# Mosquito.net
KiCad netlist of a schematic drawn in EAGLE
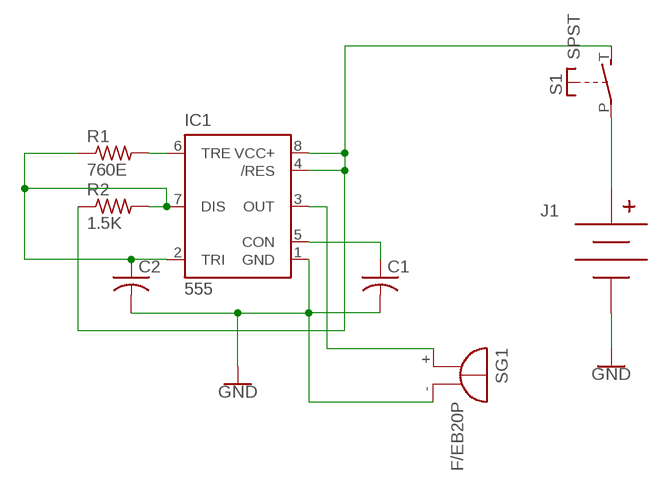
[diagram p0: schematic, sheet 1]

(export (version "E")
  (design (tool "Eeschema 10.0.6"))
  (components
    (comp (ref "C1")
      (value "C-US025-024X044")
      (footprint "eagle-import:C025-024X044")
      (libsource (lib "eagle-import") (part "C-US025-024X044"))
    )
    (comp (ref "C2")
      (value "C-US025-024X044")
      (footprint "eagle-import:C025-024X044")
      (libsource (lib "eagle-import") (part "C-US025-024X044"))
    )
    (comp (ref "IC1")
      (value "555")
      (footprint "eagle-import:DIP08")
      (libsource (lib "eagle-import") (part "555P"))
    )
    (comp (ref "J1")
      (value "BC9VPC")
      (footprint "eagle-import:BC9VPC")
      (libsource (lib "eagle-import") (part "BC9VPC"))
    )
    (comp (ref "R1")
      (value "760E")
      (footprint "eagle-import:0204V")
      (libsource (lib "eagle-import") (part "R-US_0204/2V"))
    )
    (comp (ref "R2")
      (value "1.5K")
      (footprint "eagle-import:0204V")
      (libsource (lib "eagle-import") (part "R-US_0204/2V"))
    )
    (comp (ref "S1")
      (value "SPST")
      (footprint "eagle-import:JUDCOSPST")
      (libsource (lib "eagle-import") (part "SPST"))
    )
    (comp (ref "SG1")
      (value "F/EB20P")
      (footprint "eagle-import:F_EB20P")
      (libsource (lib "eagle-import") (part "F/EB20P"))
    )
  )
  (nets
    (net (code "1") (name "GND") (class "Default")
      (node (ref "C1") (pin "2") (pinfunction "2_2") (pintype "passive"))
      (node (ref "C2") (pin "2") (pinfunction "2_2") (pintype "passive"))
      (node (ref "IC1") (pin "1") (pinfunction "GND_1") (pintype "power_in"))
      (node (ref "J1") (pin "V-") (pinfunction "V-_V-") (pintype "bidirectional"))
      (node (ref "SG1") (pin "-") (pinfunction "-_-") (pintype "passive"))
    )
    (net (code "2") (name "Net-(IC1-CON)") (class "Default")
      (node (ref "C1") (pin "1") (pinfunction "1_1") (pintype "passive"))
      (node (ref "IC1") (pin "5") (pinfunction "CON_5") (pintype "input"))
    )
    (net (code "3") (name "Net-(IC1-DIS)") (class "Default")
      (node (ref "C2") (pin "1") (pinfunction "1_1") (pintype "passive"))
      (node (ref "IC1") (pin "2") (pinfunction "TRI_2") (pintype "input"))
      (node (ref "IC1") (pin "7") (pinfunction "DIS_7") (pintype "input"))
      (node (ref "R1") (pin "1") (pinfunction "1_1") (pintype "passive"))
      (node (ref "R2") (pin "2") (pinfunction "2_2") (pintype "passive"))
    )
    (net (code "4") (name "Net-(IC1-OUT)") (class "Default")
      (node (ref "IC1") (pin "3") (pinfunction "OUT_3") (pintype "output"))
      (node (ref "SG1") (pin "+") (pinfunction "+_+") (pintype "passive"))
    )
    (net (code "5") (name "Net-(IC1-TRE)") (class "Default")
      (node (ref "IC1") (pin "6") (pinfunction "TRE_6") (pintype "input"))
      (node (ref "R1") (pin "2") (pinfunction "2_2") (pintype "passive"))
    )
    (net (code "6") (name "Net-(IC1-VCC+)") (class "Default")
      (node (ref "IC1") (pin "4") (pinfunction "/RES_4") (pintype "input"))
      (node (ref "IC1") (pin "8") (pinfunction "VCC+_8") (pintype "power_in"))
      (node (ref "R2") (pin "1") (pinfunction "1_1") (pintype "passive"))
      (node (ref "S1") (pin "T") (pinfunction "S_T") (pintype "passive"))
    )
    (net (code "7") (name "Net-(J1-PadV+)") (class "Default")
      (node (ref "J1") (pin "V+") (pinfunction "V+_V+") (pintype "bidirectional"))
      (node (ref "S1") (pin "P") (pinfunction "P_P") (pintype "passive"))
    )
  )
)
